# IMU_REV_1A.net
KiCad netlist of a schematic drawn in Altium Designer
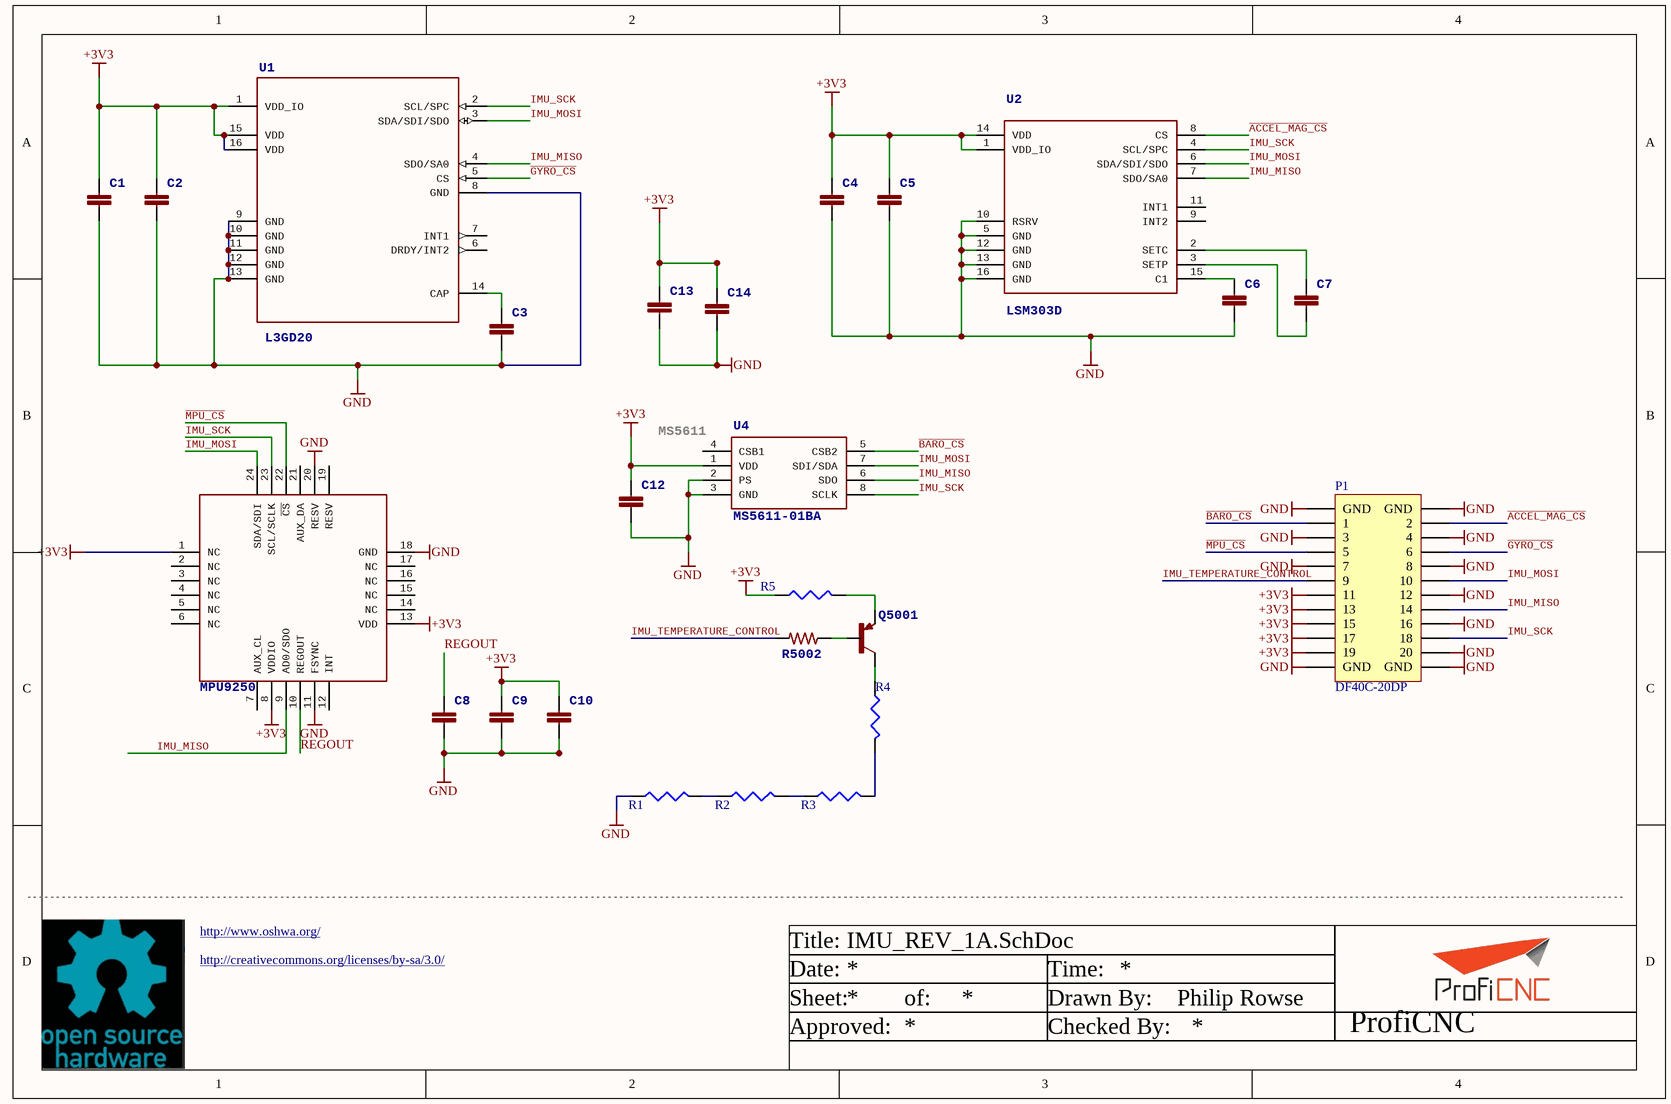
[diagram p0: IMU_REV_1A.SchDoc]

(export (version "E")
  (design (tool "Eeschema 10.0.6"))
  (components
    (comp (ref "C1") (value "~") (libsource (lib "altium-import") (part "root_0_CAPACITOR-0805_")))
    (comp (ref "C2") (value "~") (libsource (lib "altium-import") (part "root_0_CAPACITOR-0402_")))
    (comp (ref "C3") (value "~") (libsource (lib "altium-import") (part "root_0_CAPACITOR-0402_")))
    (comp (ref "C4") (value "~") (libsource (lib "altium-import") (part "root_0_CAPACITOR-0805_")))
    (comp (ref "C5") (value "~") (libsource (lib "altium-import") (part "root_0_CAPACITOR-0402_")))
    (comp (ref "C6") (value "~") (libsource (lib "altium-import") (part "root_0_CAPACITOR-0805_")))
    (comp (ref "C7") (value "~") (libsource (lib "altium-import") (part "root_0_CAPACITOR-0402_")))
    (comp (ref "C8") (value "~") (libsource (lib "altium-import") (part "root_0_CAPACITOR-0603_")))
    (comp (ref "C9") (value "~") (libsource (lib "altium-import") (part "root_0_CAPACITOR-0603_")))
    (comp (ref "C10") (value "~") (libsource (lib "altium-import") (part "root_0_CAPACITOR-0402_")))
    (comp (ref "C12") (value "~") (libsource (lib "altium-import") (part "root_0_CAPACITOR-0402_")))
    (comp (ref "C13") (value "~") (libsource (lib "altium-import") (part "root_0_CAPACITOR-0805_")))
    (comp (ref "C14") (value "~") (libsource (lib "altium-import") (part "root_0_CAPACITOR-0402_")))
    (comp (ref "MPU9250") (value "~") (libsource (lib "altium-import") (part "root_0_MPU-6500_")))
    (comp (ref "P1") (value "DF40C-20DP") (libsource (lib "altium-import") (part "root_0_DF40C-20DP_")))
    (comp (ref "Q5001") (value "~") (libsource (lib "altium-import") (part "root_0_MMBT3906*SMD_")))
    (comp (ref "R1") (value "Resistor") (libsource (lib "altium-import") (part "root_1_Resistor_")))
    (comp (ref "R2") (value "Resistor") (libsource (lib "altium-import") (part "root_1_Resistor_")))
    (comp (ref "R3") (value "Resistor") (libsource (lib "altium-import") (part "root_1_Resistor_")))
    (comp (ref "R4") (value "Resistor") (libsource (lib "altium-import") (part "root_0_Resistor_")))
    (comp (ref "R5") (value "Resistor") (libsource (lib "altium-import") (part "root_1_Resistor_")))
    (comp (ref "R5002") (value "~") (libsource (lib "altium-import") (part "root_2_RESISTOR0402-RES_")))
    (comp (ref "U1") (value "L3GD20") (libsource (lib "altium-import") (part "root_0_L3GD20_")))
    (comp (ref "U2") (value "LSM303D") (libsource (lib "altium-import") (part "root_0_LSM303D_")))
    (comp (ref "U4") (value "MS5611-01BA") (libsource (lib "altium-import") (part "root_0_MS5611-01BA_")))
  )
  (nets
    (net (code "1") (name "+3V3") (class "Default")
      (node (ref "C1") (pin "P$1") (pinfunction "1_P$1") (pintype "passive"))
      (node (ref "C10") (pin "P$1") (pinfunction "1_P$1") (pintype "passive"))
      (node (ref "C12") (pin "P$1") (pinfunction "1_P$1") (pintype "passive"))
      (node (ref "C13") (pin "P$1") (pinfunction "1_P$1") (pintype "passive"))
      (node (ref "C14") (pin "P$1") (pinfunction "1_P$1") (pintype "passive"))
      (node (ref "C2") (pin "P$1") (pinfunction "1_P$1") (pintype "passive"))
      (node (ref "C4") (pin "P$1") (pinfunction "1_P$1") (pintype "passive"))
      (node (ref "C5") (pin "P$1") (pinfunction "1_P$1") (pintype "passive"))
      (node (ref "C9") (pin "P$1") (pinfunction "1_P$1") (pintype "passive"))
      (node (ref "MPU9250") (pin "1") (pinfunction "NC_1") (pintype "passive"))
      (node (ref "MPU9250") (pin "13") (pinfunction "VDD_13") (pintype "passive"))
      (node (ref "MPU9250") (pin "8") (pinfunction "VDDIO_8") (pintype "passive"))
      (node (ref "P1") (pin "11") (pinfunction "11_11") (pintype "passive"))
      (node (ref "P1") (pin "13") (pinfunction "13_13") (pintype "passive"))
      (node (ref "P1") (pin "15") (pinfunction "15_15") (pintype "passive"))
      (node (ref "P1") (pin "17") (pinfunction "17_17") (pintype "passive"))
      (node (ref "P1") (pin "19") (pinfunction "19_19") (pintype "passive"))
      (node (ref "R5") (pin "1") (pinfunction "1_1") (pintype "passive"))
      (node (ref "U1") (pin "1") (pinfunction "VDD_IO_1") (pintype "power_in"))
      (node (ref "U1") (pin "15") (pinfunction "VDD_15") (pintype "power_in"))
      (node (ref "U1") (pin "16") (pinfunction "VDD_16") (pintype "power_in"))
      (node (ref "U2") (pin "1") (pinfunction "VDD_IO_1") (pintype "passive"))
      (node (ref "U2") (pin "14") (pinfunction "VDD_14") (pintype "passive"))
      (node (ref "U4") (pin "1") (pinfunction "VDD_1") (pintype "passive"))
    )
    (net (code "2") (name "/IMU_MISO") (class "Default")
      (node (ref "MPU9250") (pin "9") (pinfunction "AD0/SDO_9") (pintype "passive"))
      (node (ref "P1") (pin "14") (pinfunction "14_14") (pintype "passive"))
      (node (ref "U1") (pin "4") (pinfunction "SDO/SA0_4") (pintype "input"))
      (node (ref "U2") (pin "7") (pinfunction "SDO/SA0_7") (pintype "passive"))
      (node (ref "U4") (pin "6") (pinfunction "SDO_6") (pintype "passive"))
    )
    (net (code "3") (name "/IMU_MOSI") (class "Default")
      (node (ref "MPU9250") (pin "24") (pinfunction "SDA/SDI_24") (pintype "passive"))
      (node (ref "P1") (pin "10") (pinfunction "10_10") (pintype "passive"))
      (node (ref "U1") (pin "3") (pinfunction "SDA/SDI/SDO_3") (pintype "bidirectional"))
      (node (ref "U2") (pin "6") (pinfunction "SDA/SDI/SDO_6") (pintype "passive"))
      (node (ref "U4") (pin "7") (pinfunction "SDI/SDA_7") (pintype "passive"))
    )
    (net (code "4") (name "/IMU_SCK") (class "Default")
      (node (ref "MPU9250") (pin "23") (pinfunction "SCL/SCLK_23") (pintype "passive"))
      (node (ref "P1") (pin "18") (pinfunction "18_18") (pintype "passive"))
      (node (ref "U1") (pin "2") (pinfunction "SCL/SPC_2") (pintype "input"))
      (node (ref "U2") (pin "4") (pinfunction "SCL/SPC_4") (pintype "passive"))
      (node (ref "U4") (pin "8") (pinfunction "SCLK_8") (pintype "passive"))
    )
    (net (code "5") (name "/IMU_TEMPERATURE_CONTROL") (class "Default")
      (node (ref "P1") (pin "9") (pinfunction "9_9") (pintype "passive"))
      (node (ref "R5002") (pin "P$2") (pinfunction "2_P$2") (pintype "passive"))
    )
    (net (code "6") (name "/REGOUT") (class "Default")
      (node (ref "C8") (pin "P$1") (pinfunction "1_P$1") (pintype "passive"))
      (node (ref "MPU9250") (pin "10") (pinfunction "REGOUT_10") (pintype "passive"))
    )
    (net (code "7") (name "/~{ACCEL_MAG_CS}") (class "Default")
      (node (ref "P1") (pin "2") (pinfunction "2_2") (pintype "passive"))
      (node (ref "U2") (pin "8") (pinfunction "CS_8") (pintype "passive"))
    )
    (net (code "8") (name "/~{BARO_CS}") (class "Default")
      (node (ref "P1") (pin "1") (pinfunction "1_1") (pintype "passive"))
      (node (ref "U4") (pin "5") (pinfunction "CSB2_5") (pintype "passive"))
    )
    (net (code "9") (name "/~{GYRO_CS}") (class "Default")
      (node (ref "P1") (pin "6") (pinfunction "6_6") (pintype "passive"))
      (node (ref "U1") (pin "5") (pinfunction "CS_5") (pintype "input"))
    )
    (net (code "10") (name "/~{MPU_CS}") (class "Default")
      (node (ref "MPU9250") (pin "22") (pinfunction "~{CS}_22") (pintype "passive"))
      (node (ref "P1") (pin "5") (pinfunction "5_5") (pintype "passive"))
    )
    (net (code "11") (name "GND") (class "Default")
      (node (ref "C1") (pin "P$2") (pinfunction "2_P$2") (pintype "passive"))
      (node (ref "C10") (pin "P$2") (pinfunction "2_P$2") (pintype "passive"))
      (node (ref "C12") (pin "P$2") (pinfunction "2_P$2") (pintype "passive"))
      (node (ref "C13") (pin "P$2") (pinfunction "2_P$2") (pintype "passive"))
      (node (ref "C14") (pin "P$2") (pinfunction "2_P$2") (pintype "passive"))
      (node (ref "C2") (pin "P$2") (pinfunction "2_P$2") (pintype "passive"))
      (node (ref "C3") (pin "P$2") (pinfunction "2_P$2") (pintype "passive"))
      (node (ref "C4") (pin "P$2") (pinfunction "2_P$2") (pintype "passive"))
      (node (ref "C5") (pin "P$2") (pinfunction "2_P$2") (pintype "passive"))
      (node (ref "C6") (pin "P$2") (pinfunction "2_P$2") (pintype "passive"))
      (node (ref "C8") (pin "P$2") (pinfunction "2_P$2") (pintype "passive"))
      (node (ref "C9") (pin "P$2") (pinfunction "2_P$2") (pintype "passive"))
      (node (ref "MPU9250") (pin "11") (pinfunction "FSYNC_11") (pintype "passive"))
      (node (ref "MPU9250") (pin "18") (pinfunction "GND_18") (pintype "passive"))
      (node (ref "MPU9250") (pin "20") (pinfunction "RESV_20") (pintype "passive"))
      (node (ref "P1") (pin "12") (pinfunction "12_12") (pintype "passive"))
      (node (ref "P1") (pin "16") (pinfunction "16_16") (pintype "passive"))
      (node (ref "P1") (pin "20") (pinfunction "20_20") (pintype "passive"))
      (node (ref "P1") (pin "21") (pinfunction "GND_21") (pintype "passive"))
      (node (ref "P1") (pin "22") (pinfunction "GND_22") (pintype "passive"))
      (node (ref "P1") (pin "23") (pinfunction "GND_23") (pintype "passive"))
      (node (ref "P1") (pin "24") (pinfunction "GND_24") (pintype "passive"))
      (node (ref "P1") (pin "3") (pinfunction "3_3") (pintype "passive"))
      (node (ref "P1") (pin "4") (pinfunction "4_4") (pintype "passive"))
      (node (ref "P1") (pin "7") (pinfunction "7_7") (pintype "passive"))
      (node (ref "P1") (pin "8") (pinfunction "8_8") (pintype "passive"))
      (node (ref "R1") (pin "1") (pinfunction "1_1") (pintype "passive"))
      (node (ref "U1") (pin "10") (pinfunction "GND_10") (pintype "power_in"))
      (node (ref "U1") (pin "11") (pinfunction "GND_11") (pintype "power_in"))
      (node (ref "U1") (pin "12") (pinfunction "GND_12") (pintype "power_in"))
      (node (ref "U1") (pin "13") (pinfunction "GND_13") (pintype "power_in"))
      (node (ref "U1") (pin "8") (pinfunction "GND_8") (pintype "power_in"))
      (node (ref "U1") (pin "9") (pinfunction "GND_9") (pintype "power_in"))
      (node (ref "U2") (pin "10") (pinfunction "RSRV_10") (pintype "passive"))
      (node (ref "U2") (pin "12") (pinfunction "GND_12") (pintype "passive"))
      (node (ref "U2") (pin "13") (pinfunction "GND_13") (pintype "passive"))
      (node (ref "U2") (pin "16") (pinfunction "GND_16") (pintype "passive"))
      (node (ref "U2") (pin "5") (pinfunction "GND_5") (pintype "passive"))
      (node (ref "U4") (pin "2") (pinfunction "PS_2") (pintype "passive"))
      (node (ref "U4") (pin "3") (pinfunction "GND_3") (pintype "passive"))
    )
    (net (code "12") (name "Net-(C3-1)") (class "Default")
      (node (ref "C3") (pin "P$1") (pinfunction "1_P$1") (pintype "passive"))
      (node (ref "U1") (pin "14") (pinfunction "CAP_14") (pintype "passive"))
    )
    (net (code "13") (name "Net-(C6-1)") (class "Default")
      (node (ref "C6") (pin "P$1") (pinfunction "1_P$1") (pintype "passive"))
      (node (ref "U2") (pin "15") (pinfunction "C1_15") (pintype "passive"))
    )
    (net (code "14") (name "Net-(C7-1)") (class "Default")
      (node (ref "C7") (pin "P$1") (pinfunction "1_P$1") (pintype "passive"))
      (node (ref "U2") (pin "2") (pinfunction "SETC_2") (pintype "passive"))
    )
    (net (code "15") (name "Net-(C7-2)") (class "Default")
      (node (ref "C7") (pin "P$2") (pinfunction "2_P$2") (pintype "passive"))
      (node (ref "U2") (pin "3") (pinfunction "SETP_3") (pintype "passive"))
    )
    (net (code "16") (name "Net-(Q5001-PadC)") (class "Default")
      (node (ref "Q5001") (pin "C") (pinfunction "C_C") (pintype "passive"))
      (node (ref "R4") (pin "1") (pinfunction "1_1") (pintype "passive"))
    )
    (net (code "17") (name "Net-(Q5001-PadE)") (class "Default")
      (node (ref "Q5001") (pin "E") (pinfunction "E_E") (pintype "passive"))
      (node (ref "R5") (pin "2") (pinfunction "2_2") (pintype "passive"))
    )
    (net (code "18") (name "Net-(R1-Pad2)") (class "Default")
      (node (ref "R1") (pin "2") (pinfunction "2_2") (pintype "passive"))
      (node (ref "R2") (pin "1") (pinfunction "1_1") (pintype "passive"))
    )
    (net (code "19") (name "Net-(R2-Pad2)") (class "Default")
      (node (ref "R2") (pin "2") (pinfunction "2_2") (pintype "passive"))
      (node (ref "R3") (pin "1") (pinfunction "1_1") (pintype "passive"))
    )
    (net (code "20") (name "Net-(R3-Pad2)") (class "Default")
      (node (ref "R3") (pin "2") (pinfunction "2_2") (pintype "passive"))
      (node (ref "R4") (pin "2") (pinfunction "2_2") (pintype "passive"))
    )
    (net (code "21") (name "Net-(R5002-1)") (class "Default")
      (node (ref "Q5001") (pin "B") (pinfunction "B_B") (pintype "passive"))
      (node (ref "R5002") (pin "P$1") (pinfunction "1_P$1") (pintype "passive"))
    )
    (net (code "22") (name "unconnected-(MPU9250-AUX_CL-Pad7)") (class "Default")
      (node (ref "MPU9250") (pin "7") (pinfunction "AUX_CL_7") (pintype "passive"))
    )
    (net (code "23") (name "unconnected-(MPU9250-AUX_DA-Pad21)") (class "Default")
      (node (ref "MPU9250") (pin "21") (pinfunction "AUX_DA_21") (pintype "passive"))
    )
    (net (code "24") (name "unconnected-(MPU9250-INT-Pad12)") (class "Default")
      (node (ref "MPU9250") (pin "12") (pinfunction "INT_12") (pintype "passive"))
    )
    (net (code "25") (name "unconnected-(MPU9250-NC-Pad2)") (class "Default")
      (node (ref "MPU9250") (pin "2") (pinfunction "NC_2") (pintype "passive"))
    )
    (net (code "26") (name "unconnected-(MPU9250-NC-Pad3)") (class "Default")
      (node (ref "MPU9250") (pin "3") (pinfunction "NC_3") (pintype "passive"))
    )
    (net (code "27") (name "unconnected-(MPU9250-NC-Pad4)") (class "Default")
      (node (ref "MPU9250") (pin "4") (pinfunction "NC_4") (pintype "passive"))
    )
    (net (code "28") (name "unconnected-(MPU9250-NC-Pad5)") (class "Default")
      (node (ref "MPU9250") (pin "5") (pinfunction "NC_5") (pintype "passive"))
    )
    (net (code "29") (name "unconnected-(MPU9250-NC-Pad6)") (class "Default")
      (node (ref "MPU9250") (pin "6") (pinfunction "NC_6") (pintype "passive"))
    )
    (net (code "30") (name "unconnected-(MPU9250-NC-Pad14)") (class "Default")
      (node (ref "MPU9250") (pin "14") (pinfunction "NC_14") (pintype "passive"))
    )
    (net (code "31") (name "unconnected-(MPU9250-NC-Pad15)") (class "Default")
      (node (ref "MPU9250") (pin "15") (pinfunction "NC_15") (pintype "passive"))
    )
    (net (code "32") (name "unconnected-(MPU9250-NC-Pad16)") (class "Default")
      (node (ref "MPU9250") (pin "16") (pinfunction "NC_16") (pintype "passive"))
    )
    (net (code "33") (name "unconnected-(MPU9250-NC-Pad17)") (class "Default")
      (node (ref "MPU9250") (pin "17") (pinfunction "NC_17") (pintype "passive"))
    )
    (net (code "34") (name "unconnected-(MPU9250-RESV-Pad19)") (class "Default")
      (node (ref "MPU9250") (pin "19") (pinfunction "RESV_19") (pintype "passive"))
    )
    (net (code "35") (name "unconnected-(U1-DRDY{slash}INT2-Pad6)") (class "Default")
      (node (ref "U1") (pin "6") (pinfunction "DRDY/INT2_6") (pintype "output"))
    )
    (net (code "36") (name "unconnected-(U1-INT1-Pad7)") (class "Default")
      (node (ref "U1") (pin "7") (pinfunction "INT1_7") (pintype "output"))
    )
    (net (code "37") (name "unconnected-(U2-INT1-Pad11)") (class "Default")
      (node (ref "U2") (pin "11") (pinfunction "INT1_11") (pintype "passive"))
    )
    (net (code "38") (name "unconnected-(U2-INT2-Pad9)") (class "Default")
      (node (ref "U2") (pin "9") (pinfunction "INT2_9") (pintype "passive"))
    )
    (net (code "39") (name "unconnected-(U4-CSB1-Pad4)") (class "Default")
      (node (ref "U4") (pin "4") (pinfunction "CSB1_4") (pintype "passive"))
    )
  )
)
